# PCB-Neopixel_Control.net
KiCad netlist of a schematic drawn in EAGLE
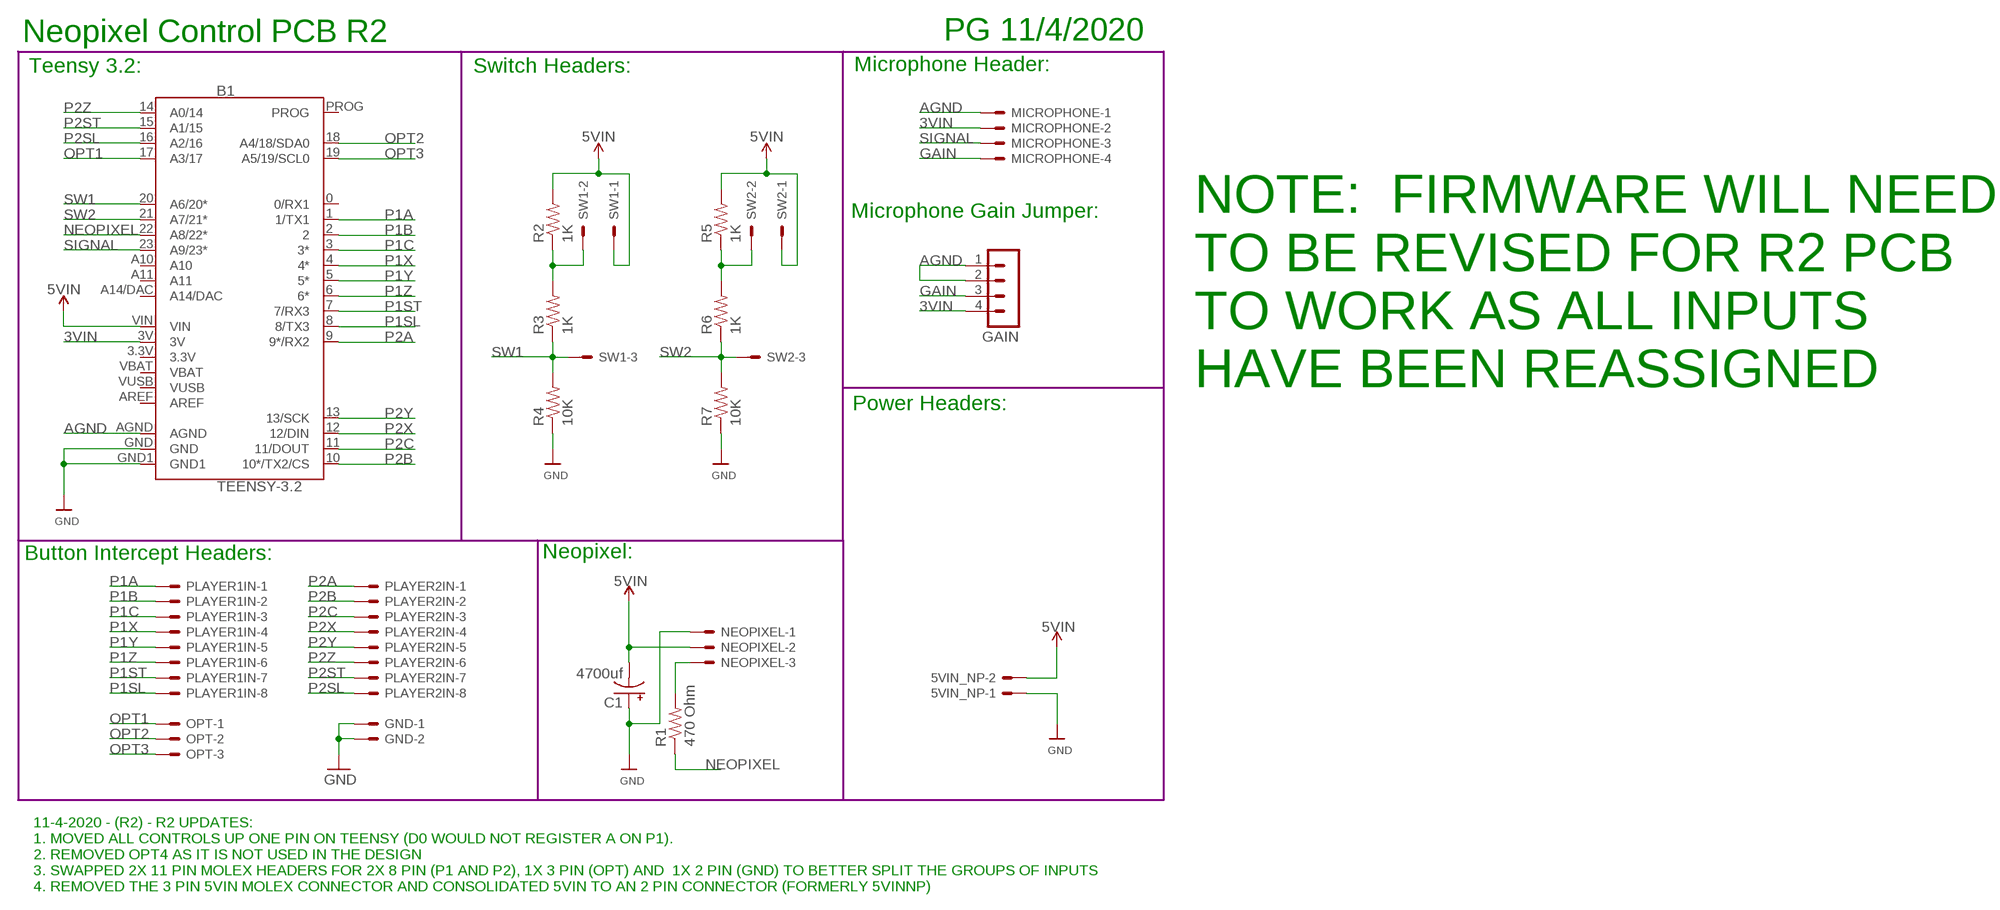
[diagram p0: schematic, sheet 1]

(export (version "E")
  (design (tool "Eeschema 10.0.6"))
  (components
    (comp (ref "5VIN_NP")
      (value "KK-156-2")
      (footprint "eagle-import:KK-156-2")
      (fields (field (name "MF") "MOLEX"))
      (libsource (lib "eagle-import") (part "KK-156-2"))
    )
    (comp (ref "B1")
      (value "TEENSY-3.2")
      (footprint "eagle-import:TEENSY-3.1")
      (libsource (lib "eagle-import") (part "TEENSY-3.1SILK"))
    )
    (comp (ref "C1")
      (value "4700uf")
      (footprint "eagle-import:E5-13")
      (libsource (lib "eagle-import") (part "CPOL-USE5-13"))
    )
    (comp (ref "GAIN")
      (value "MA04-1")
      (footprint "eagle-import:MA04-1")
      (libsource (lib "eagle-import") (part "MA04-1"))
    )
    (comp (ref "GND")
      (value "KK-156-2")
      (footprint "eagle-import:KK-156-2")
      (fields (field (name "MF") "MOLEX"))
      (libsource (lib "eagle-import") (part "KK-156-2"))
    )
    (comp (ref "MICROPHONE")
      (value "KK-156-4")
      (footprint "eagle-import:KK-156-4")
      (fields (field (name "MF") "MOLEX"))
      (libsource (lib "eagle-import") (part "KK-156-4"))
    )
    (comp (ref "NEOPIXEL")
      (value "KK-156-3")
      (footprint "eagle-import:KK-156-3")
      (fields (field (name "MF") "MOLEX"))
      (libsource (lib "eagle-import") (part "KK-156-3"))
    )
    (comp (ref "OPT")
      (value "KK-156-3")
      (footprint "eagle-import:KK-156-3")
      (fields (field (name "MF") "MOLEX"))
      (libsource (lib "eagle-import") (part "KK-156-3"))
    )
    (comp (ref "PLAYER1IN")
      (value "KK-156-8")
      (footprint "eagle-import:KK-156-8")
      (fields (field (name "MF") "MOLEX"))
      (libsource (lib "eagle-import") (part "KK-156-8"))
    )
    (comp (ref "PLAYER2IN")
      (value "KK-156-8")
      (footprint "eagle-import:KK-156-8")
      (fields (field (name "MF") "MOLEX"))
      (libsource (lib "eagle-import") (part "KK-156-8"))
    )
    (comp (ref "R1")
      (value "470 Ohm")
      (footprint "eagle-import:R1206")
      (libsource (lib "eagle-import") (part "R-US_R1206"))
    )
    (comp (ref "R2")
      (value "1K")
      (footprint "eagle-import:R1206")
      (libsource (lib "eagle-import") (part "R-US_R1206"))
    )
    (comp (ref "R3")
      (value "1K")
      (footprint "eagle-import:R1206")
      (libsource (lib "eagle-import") (part "R-US_R1206"))
    )
    (comp (ref "R4")
      (value "10K")
      (footprint "eagle-import:R1206")
      (libsource (lib "eagle-import") (part "R-US_R1206"))
    )
    (comp (ref "R5")
      (value "1K")
      (footprint "eagle-import:R1206")
      (libsource (lib "eagle-import") (part "R-US_R1206"))
    )
    (comp (ref "R6")
      (value "1K")
      (footprint "eagle-import:R1206")
      (libsource (lib "eagle-import") (part "R-US_R1206"))
    )
    (comp (ref "R7")
      (value "10K")
      (footprint "eagle-import:R1206")
      (libsource (lib "eagle-import") (part "R-US_R1206"))
    )
    (comp (ref "SW1")
      (value "KK-156-3")
      (footprint "eagle-import:KK-156-3")
      (fields (field (name "MF") "MOLEX"))
      (libsource (lib "eagle-import") (part "KK-156-3"))
    )
    (comp (ref "SW2")
      (value "KK-156-3")
      (footprint "eagle-import:KK-156-3")
      (fields (field (name "MF") "MOLEX"))
      (libsource (lib "eagle-import") (part "KK-156-3"))
    )
  )
  (nets
    (net (code "1") (name "/3.3V") (class "Default")
      (node (ref "B1") (pin "3.3V") (pinfunction "3.3V_3.3V") (pintype "power_in"))
    )
    (net (code "2") (name "/3VIN") (class "Default")
      (node (ref "B1") (pin "3V") (pinfunction "3V_3V") (pintype "power_in"))
      (node (ref "GAIN") (pin "4") (pinfunction "4_4") (pintype "passive"))
      (node (ref "MICROPHONE") (pin "2") (pinfunction "S_2") (pintype "passive"))
    )
    (net (code "3") (name "/AGND") (class "Default")
      (node (ref "B1") (pin "AGND") (pinfunction "AGND_AGND") (pintype "power_in"))
      (node (ref "GAIN") (pin "1") (pinfunction "1_1") (pintype "passive"))
      (node (ref "GAIN") (pin "2") (pinfunction "2_2") (pintype "passive"))
      (node (ref "MICROPHONE") (pin "1") (pinfunction "S_1") (pintype "passive"))
    )
    (net (code "4") (name "/GAIN") (class "Default")
      (node (ref "GAIN") (pin "3") (pinfunction "3_3") (pintype "passive"))
      (node (ref "MICROPHONE") (pin "4") (pinfunction "S_4") (pintype "passive"))
    )
    (net (code "5") (name "/NEOPIXEL") (class "Default")
      (node (ref "B1") (pin "22") (pinfunction "A8/22*_22") (pintype "bidirectional"))
      (node (ref "R1") (pin "1") (pinfunction "1_1") (pintype "passive"))
    )
    (net (code "6") (name "/OPT1") (class "Default")
      (node (ref "B1") (pin "17") (pinfunction "A3/17_17") (pintype "bidirectional"))
      (node (ref "OPT") (pin "1") (pinfunction "S_1") (pintype "passive"))
    )
    (net (code "7") (name "/OPT2") (class "Default")
      (node (ref "B1") (pin "18") (pinfunction "A4/18/SDA0_18") (pintype "bidirectional"))
      (node (ref "OPT") (pin "2") (pinfunction "S_2") (pintype "passive"))
    )
    (net (code "8") (name "/OPT3") (class "Default")
      (node (ref "B1") (pin "19") (pinfunction "A5/19/SCL0_19") (pintype "bidirectional"))
      (node (ref "OPT") (pin "3") (pinfunction "S_3") (pintype "passive"))
    )
    (net (code "9") (name "/P1A") (class "Default")
      (node (ref "B1") (pin "1") (pinfunction "1/TX1_1") (pintype "bidirectional"))
      (node (ref "PLAYER1IN") (pin "1") (pinfunction "S_1") (pintype "passive"))
    )
    (net (code "10") (name "/P1B") (class "Default")
      (node (ref "B1") (pin "2") (pinfunction "2_2") (pintype "bidirectional"))
      (node (ref "PLAYER1IN") (pin "2") (pinfunction "S_2") (pintype "passive"))
    )
    (net (code "11") (name "/P1C") (class "Default")
      (node (ref "B1") (pin "3") (pinfunction "3*_3") (pintype "bidirectional"))
      (node (ref "PLAYER1IN") (pin "3") (pinfunction "S_3") (pintype "passive"))
    )
    (net (code "12") (name "/P1SL") (class "Default")
      (node (ref "B1") (pin "8") (pinfunction "8/TX3_8") (pintype "bidirectional"))
      (node (ref "PLAYER1IN") (pin "8") (pinfunction "S_8") (pintype "passive"))
    )
    (net (code "13") (name "/P1ST") (class "Default")
      (node (ref "B1") (pin "7") (pinfunction "7/RX3_7") (pintype "bidirectional"))
      (node (ref "PLAYER1IN") (pin "7") (pinfunction "S_7") (pintype "passive"))
    )
    (net (code "14") (name "/P1X") (class "Default")
      (node (ref "B1") (pin "4") (pinfunction "4*_4") (pintype "bidirectional"))
      (node (ref "PLAYER1IN") (pin "4") (pinfunction "S_4") (pintype "passive"))
    )
    (net (code "15") (name "/P1Y") (class "Default")
      (node (ref "B1") (pin "5") (pinfunction "5*_5") (pintype "bidirectional"))
      (node (ref "PLAYER1IN") (pin "5") (pinfunction "S_5") (pintype "passive"))
    )
    (net (code "16") (name "/P1Z") (class "Default")
      (node (ref "B1") (pin "6") (pinfunction "6*_6") (pintype "bidirectional"))
      (node (ref "PLAYER1IN") (pin "6") (pinfunction "S_6") (pintype "passive"))
    )
    (net (code "17") (name "/P2A") (class "Default")
      (node (ref "B1") (pin "9") (pinfunction "9*/RX2_9") (pintype "bidirectional"))
      (node (ref "PLAYER2IN") (pin "1") (pinfunction "S_1") (pintype "passive"))
    )
    (net (code "18") (name "/P2B") (class "Default")
      (node (ref "B1") (pin "10") (pinfunction "10*/TX2/CS_10") (pintype "bidirectional"))
      (node (ref "PLAYER2IN") (pin "2") (pinfunction "S_2") (pintype "passive"))
    )
    (net (code "19") (name "/P2C") (class "Default")
      (node (ref "B1") (pin "11") (pinfunction "11/DOUT_11") (pintype "bidirectional"))
      (node (ref "PLAYER2IN") (pin "3") (pinfunction "S_3") (pintype "passive"))
    )
    (net (code "20") (name "/P2SL") (class "Default")
      (node (ref "B1") (pin "16") (pinfunction "A2/16_16") (pintype "bidirectional"))
      (node (ref "PLAYER2IN") (pin "8") (pinfunction "S_8") (pintype "passive"))
    )
    (net (code "21") (name "/P2ST") (class "Default")
      (node (ref "B1") (pin "15") (pinfunction "A1/15_15") (pintype "bidirectional"))
      (node (ref "PLAYER2IN") (pin "7") (pinfunction "S_7") (pintype "passive"))
    )
    (net (code "22") (name "/P2X") (class "Default")
      (node (ref "B1") (pin "12") (pinfunction "12/DIN_12") (pintype "bidirectional"))
      (node (ref "PLAYER2IN") (pin "4") (pinfunction "S_4") (pintype "passive"))
    )
    (net (code "23") (name "/P2Y") (class "Default")
      (node (ref "B1") (pin "13") (pinfunction "13/SCK_13") (pintype "bidirectional"))
      (node (ref "PLAYER2IN") (pin "5") (pinfunction "S_5") (pintype "passive"))
    )
    (net (code "24") (name "/P2Z") (class "Default")
      (node (ref "B1") (pin "14") (pinfunction "A0/14_14") (pintype "bidirectional"))
      (node (ref "PLAYER2IN") (pin "6") (pinfunction "S_6") (pintype "passive"))
    )
    (net (code "25") (name "/SIGNAL") (class "Default")
      (node (ref "B1") (pin "23") (pinfunction "A9/23*_23") (pintype "bidirectional"))
      (node (ref "MICROPHONE") (pin "3") (pinfunction "S_3") (pintype "passive"))
    )
    (net (code "26") (name "/SW1") (class "Default")
      (node (ref "B1") (pin "20") (pinfunction "A6/20*_20") (pintype "bidirectional"))
      (node (ref "R3") (pin "1") (pinfunction "1_1") (pintype "passive"))
      (node (ref "R4") (pin "2") (pinfunction "2_2") (pintype "passive"))
      (node (ref "SW1") (pin "3") (pinfunction "S_3") (pintype "passive"))
    )
    (net (code "27") (name "/SW2") (class "Default")
      (node (ref "B1") (pin "21") (pinfunction "A7/21*_21") (pintype "bidirectional"))
      (node (ref "R6") (pin "1") (pinfunction "1_1") (pintype "passive"))
      (node (ref "R7") (pin "2") (pinfunction "2_2") (pintype "passive"))
      (node (ref "SW2") (pin "3") (pinfunction "S_3") (pintype "passive"))
    )
    (net (code "28") (name "/VBAT") (class "Default")
      (node (ref "B1") (pin "VBAT") (pinfunction "VBAT_VBAT") (pintype "power_in"))
    )
    (net (code "29") (name "/VUSB") (class "Default")
      (node (ref "B1") (pin "VUSB") (pinfunction "VUSB_VUSB") (pintype "power_in"))
    )
    (net (code "30") (name "5VIN") (class "Default")
      (node (ref "5VIN_NP") (pin "2") (pinfunction "S_2") (pintype "passive"))
      (node (ref "B1") (pin "VIN") (pinfunction "VIN_VIN") (pintype "power_in"))
      (node (ref "C1") (pin "-") (pinfunction "-_-") (pintype "passive"))
      (node (ref "NEOPIXEL") (pin "2") (pinfunction "S_2") (pintype "passive"))
      (node (ref "R2") (pin "2") (pinfunction "2_2") (pintype "passive"))
      (node (ref "R5") (pin "2") (pinfunction "2_2") (pintype "passive"))
      (node (ref "SW1") (pin "1") (pinfunction "S_1") (pintype "passive"))
      (node (ref "SW2") (pin "1") (pinfunction "S_1") (pintype "passive"))
    )
    (net (code "31") (name "GND") (class "Default")
      (node (ref "5VIN_NP") (pin "1") (pinfunction "S_1") (pintype "passive"))
      (node (ref "B1") (pin "GND") (pinfunction "GND_GND") (pintype "power_in"))
      (node (ref "B1") (pin "GND1") (pinfunction "GND1_GND1") (pintype "power_in"))
      (node (ref "C1") (pin "+") (pinfunction "+_+") (pintype "passive"))
      (node (ref "GND") (pin "1") (pinfunction "S_1") (pintype "passive"))
      (node (ref "GND") (pin "2") (pinfunction "S_2") (pintype "passive"))
      (node (ref "NEOPIXEL") (pin "1") (pinfunction "S_1") (pintype "passive"))
      (node (ref "R4") (pin "1") (pinfunction "1_1") (pintype "passive"))
      (node (ref "R7") (pin "1") (pinfunction "1_1") (pintype "passive"))
    )
    (net (code "32") (name "Net-(NEOPIXELC-S)") (class "Default")
      (node (ref "NEOPIXEL") (pin "3") (pinfunction "S_3") (pintype "passive"))
      (node (ref "R1") (pin "2") (pinfunction "2_2") (pintype "passive"))
    )
    (net (code "33") (name "Net-(SW1B-S)") (class "Default")
      (node (ref "R2") (pin "1") (pinfunction "1_1") (pintype "passive"))
      (node (ref "R3") (pin "2") (pinfunction "2_2") (pintype "passive"))
      (node (ref "SW1") (pin "2") (pinfunction "S_2") (pintype "passive"))
    )
    (net (code "34") (name "Net-(SW2B-S)") (class "Default")
      (node (ref "R5") (pin "1") (pinfunction "1_1") (pintype "passive"))
      (node (ref "R6") (pin "2") (pinfunction "2_2") (pintype "passive"))
      (node (ref "SW2") (pin "2") (pinfunction "S_2") (pintype "passive"))
    )
    (net (code "35") (name "unconnected-(B1-0{slash}RX1-Pad0)") (class "Default")
      (node (ref "B1") (pin "0") (pinfunction "0/RX1_0") (pintype "bidirectional"))
    )
    (net (code "36") (name "unconnected-(B1-PadA10)") (class "Default")
      (node (ref "B1") (pin "A10") (pinfunction "A10_A10") (pintype "bidirectional"))
    )
    (net (code "37") (name "unconnected-(B1-PadA11)") (class "Default")
      (node (ref "B1") (pin "A11") (pinfunction "A11_A11") (pintype "bidirectional"))
    )
    (net (code "38") (name "unconnected-(B1-PadA14{slash}DAC)") (class "Default")
      (node (ref "B1") (pin "A14/DAC") (pinfunction "A14/DAC_A14/DAC") (pintype "bidirectional"))
    )
    (net (code "39") (name "unconnected-(B1-PadAREF)") (class "Default")
      (node (ref "B1") (pin "AREF") (pinfunction "AREF_AREF") (pintype "bidirectional"))
    )
    (net (code "40") (name "unconnected-(B1-PadPROG)") (class "Default")
      (node (ref "B1") (pin "PROG") (pinfunction "PROG_PROG") (pintype "bidirectional"))
    )
  )
)
